# ModuleSMD.net
KiCad netlist of a schematic drawn in EAGLE
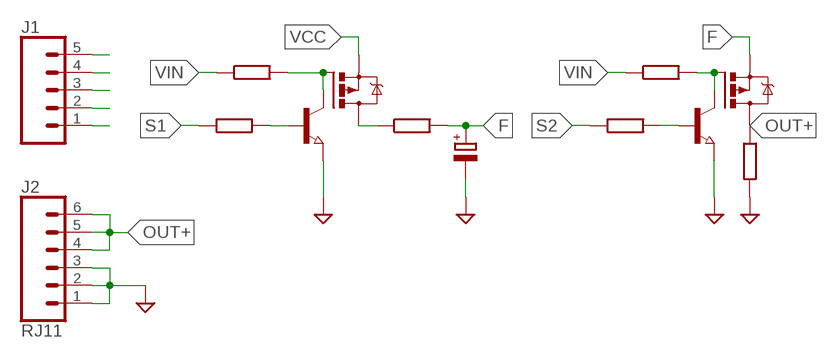
[diagram p0: schematic, sheet 1]

(export (version "E")
  (design (tool "Eeschema 10.0.6"))
  (components
    (comp (ref "C1")
      (value "CPOL-EU150CLZ-1010")
      (footprint "eagle-import:150CLZ-1010")
      (libsource (lib "eagle-import") (part "CPOL-EU150CLZ-1010"))
    )
    (comp (ref "J1")
      (value "CONN_05")
      (footprint "eagle-import:1X05")
      (libsource (lib "eagle-import") (part "CONN_05"))
    )
    (comp (ref "J2")
      (value "RJ11")
      (footprint "eagle-import:RJ11-6")
      (libsource (lib "eagle-import") (part "RJ11-6"))
    )
    (comp (ref "Q1")
      (value "IRFR5305")
      (footprint "eagle-import:D-PAK_TO252AA")
      (libsource (lib "eagle-import") (part "IRF?5305R"))
    )
    (comp (ref "Q2")
      (value "IRFR5305")
      (footprint "eagle-import:D-PAK_TO252AA")
      (libsource (lib "eagle-import") (part "IRF?5305R"))
    )
    (comp (ref "Q3")
      (value "NPN-TRANSISTOR_SOT23")
      (footprint "eagle-import:SOT23")
      (libsource (lib "eagle-import") (part "NPN-TRANSISTOR_SOT23"))
    )
    (comp (ref "Q4")
      (value "NPN-TRANSISTOR_SOT23")
      (footprint "eagle-import:SOT23")
      (libsource (lib "eagle-import") (part "NPN-TRANSISTOR_SOT23"))
    )
    (comp (ref "R1")
      (value "R-EU_01005")
      (footprint "eagle-import:R01005")
      (libsource (lib "eagle-import") (part "R-EU_01005"))
    )
    (comp (ref "R2")
      (value "R-EU_01005")
      (footprint "eagle-import:R01005")
      (libsource (lib "eagle-import") (part "R-EU_01005"))
    )
    (comp (ref "R3")
      (value "R-EU_01005")
      (footprint "eagle-import:R01005")
      (libsource (lib "eagle-import") (part "R-EU_01005"))
    )
    (comp (ref "R4")
      (value "R-EU_01005")
      (footprint "eagle-import:R01005")
      (libsource (lib "eagle-import") (part "R-EU_01005"))
    )
    (comp (ref "R5")
      (value "R-EU_01005")
      (footprint "eagle-import:R01005")
      (libsource (lib "eagle-import") (part "R-EU_01005"))
    )
    (comp (ref "R6")
      (value "R-EU_01005")
      (footprint "eagle-import:R01005")
      (libsource (lib "eagle-import") (part "R-EU_01005"))
    )
  )
  (nets
    (net (code "1") (name "F") (class "Default")
      (node (ref "C1") (pin "+") (pinfunction "+_+") (pintype "passive"))
      (node (ref "Q2") (pin "3") (pinfunction "S_3") (pintype "passive"))
      (node (ref "R5") (pin "2") (pinfunction "2_2") (pintype "passive"))
    )
    (net (code "2") (name "GND") (class "Default")
      (node (ref "C1") (pin "-") (pinfunction "-_-") (pintype "passive"))
      (node (ref "J2") (pin "1") (pinfunction "1_1") (pintype "passive"))
      (node (ref "J2") (pin "2") (pinfunction "2_2") (pintype "passive"))
      (node (ref "J2") (pin "3") (pinfunction "3_3") (pintype "passive"))
      (node (ref "Q3") (pin "2") (pinfunction "E_2") (pintype "passive"))
      (node (ref "Q4") (pin "2") (pinfunction "E_2") (pintype "passive"))
      (node (ref "R6") (pin "2") (pinfunction "2_2") (pintype "passive"))
    )
    (net (code "3") (name "Net-(Q1-D)") (class "Default")
      (node (ref "Q1") (pin "4") (pinfunction "D_4") (pintype "passive"))
      (node (ref "R5") (pin "1") (pinfunction "1_1") (pintype "passive"))
    )
    (net (code "4") (name "Net-(Q1-G)") (class "Default")
      (node (ref "Q1") (pin "1") (pinfunction "G_1") (pintype "passive"))
      (node (ref "Q3") (pin "3") (pinfunction "C_3") (pintype "passive"))
      (node (ref "R1") (pin "2") (pinfunction "2_2") (pintype "passive"))
    )
    (net (code "5") (name "Net-(Q2-G)") (class "Default")
      (node (ref "Q2") (pin "1") (pinfunction "G_1") (pintype "passive"))
      (node (ref "Q4") (pin "3") (pinfunction "C_3") (pintype "passive"))
      (node (ref "R2") (pin "2") (pinfunction "2_2") (pintype "passive"))
    )
    (net (code "6") (name "Net-(Q3-B)") (class "Default")
      (node (ref "Q3") (pin "1") (pinfunction "B_1") (pintype "passive"))
      (node (ref "R3") (pin "2") (pinfunction "2_2") (pintype "passive"))
    )
    (net (code "7") (name "Net-(Q4-B)") (class "Default")
      (node (ref "Q4") (pin "1") (pinfunction "B_1") (pintype "passive"))
      (node (ref "R4") (pin "2") (pinfunction "2_2") (pintype "passive"))
    )
    (net (code "8") (name "OUT+") (class "Default")
      (node (ref "J2") (pin "4") (pinfunction "4_4") (pintype "passive"))
      (node (ref "J2") (pin "5") (pinfunction "5_5") (pintype "passive"))
      (node (ref "J2") (pin "6") (pinfunction "6_6") (pintype "passive"))
      (node (ref "Q2") (pin "4") (pinfunction "D_4") (pintype "passive"))
      (node (ref "R6") (pin "1") (pinfunction "1_1") (pintype "passive"))
    )
    (net (code "9") (name "S1") (class "Default")
      (node (ref "R3") (pin "1") (pinfunction "1_1") (pintype "passive"))
    )
    (net (code "10") (name "S2") (class "Default")
      (node (ref "R4") (pin "1") (pinfunction "1_1") (pintype "passive"))
    )
    (net (code "11") (name "VCC") (class "Default")
      (node (ref "Q1") (pin "3") (pinfunction "S_3") (pintype "passive"))
    )
    (net (code "12") (name "VIN") (class "Default")
      (node (ref "R1") (pin "1") (pinfunction "1_1") (pintype "passive"))
      (node (ref "R2") (pin "1") (pinfunction "1_1") (pintype "passive"))
    )
    (net (code "13") (name "unconnected-(J1-Pad1)") (class "Default")
      (node (ref "J1") (pin "1") (pinfunction "1_1") (pintype "passive"))
    )
    (net (code "14") (name "unconnected-(J1-Pad2)") (class "Default")
      (node (ref "J1") (pin "2") (pinfunction "2_2") (pintype "passive"))
    )
    (net (code "15") (name "unconnected-(J1-Pad3)") (class "Default")
      (node (ref "J1") (pin "3") (pinfunction "3_3") (pintype "passive"))
    )
    (net (code "16") (name "unconnected-(J1-Pad4)") (class "Default")
      (node (ref "J1") (pin "4") (pinfunction "4_4") (pintype "passive"))
    )
    (net (code "17") (name "unconnected-(J1-Pad5)") (class "Default")
      (node (ref "J1") (pin "5") (pinfunction "5_5") (pintype "passive"))
    )
  )
)
